# Board.net
KiCad netlist of a schematic drawn in Altium Designer
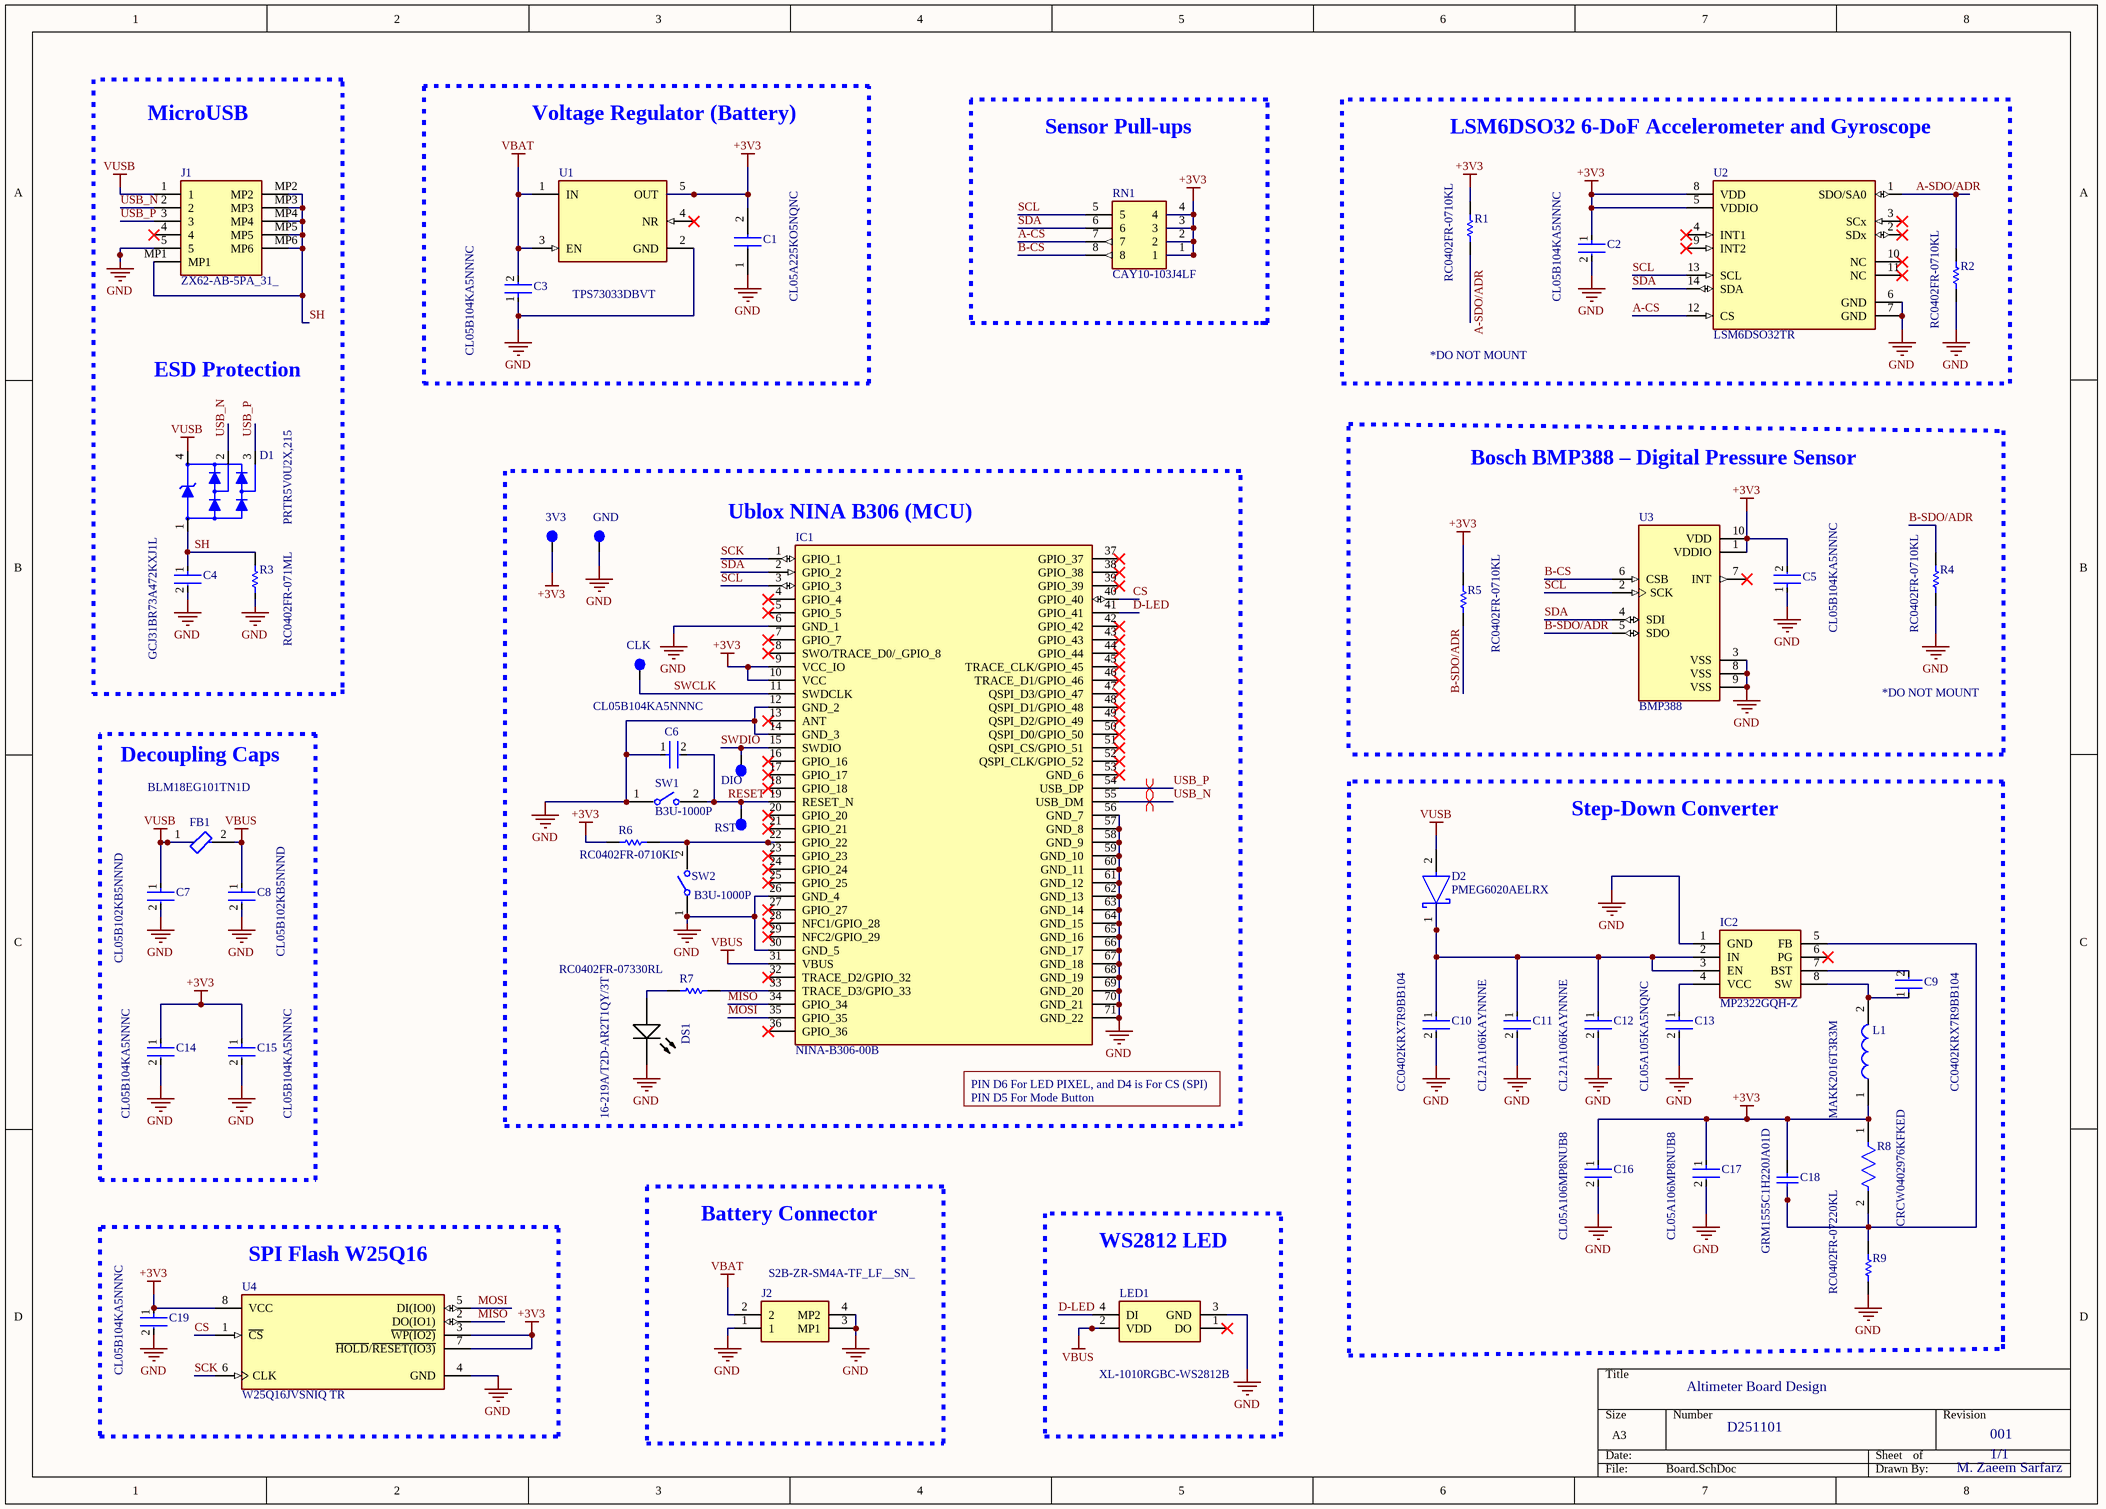
[diagram p0: Board.SchDoc]

(export (version "E")
  (design (tool "Eeschema 10.0.6"))
  (components
    (comp (ref "3V3") (value "TP_1") (footprint "TestPoint1") (libsource (lib "Schlib1") (part "TESTPOINT1")))
    (comp (ref "C1")
      (value "CL05A225KO5NQNC")
      (footprint "SamacSys:CAPC1005X60N")
      (description "Capacitor")
      (libsource (lib "*") (part "CL05A225KO5NQNC"))
    )
    (comp (ref "C2")
      (value "CL05B104KA5NNNC")
      (footprint "FP-CL830-IPC_C")
      (description "Cap Ceramic 100nF 25V X7R ±10% SMD 0402 +125°C Paper T/R")
      (fields (field (name "TOLERANCE") "10%"))
      (libsource (lib "Altium Content Vault") (part "b4654b650e69147ec39a6b967a45e02"))
    )
    (comp (ref "C3")
      (value "CL05B104KA5NNNC")
      (footprint "FP-CL830-IPC_C")
      (description "Cap Ceramic 100nF 25V X7R ±10% SMD 0402 +125°C Paper T/R")
      (fields (field (name "TOLERANCE") "10%"))
      (libsource (lib "Altium Content Vault") (part "b4654b650e69147ec39a6b967a45e02"))
    )
    (comp (ref "C4")
      (value "GCJ31BR73A472KXJ1L")
      (footprint "FP-GCJ31B-0_2-MFG")
      (description "4700pF ±10%  1kV Ceramic Capacitor X7R 1206 (3216 Metric)")
      (fields (field (name "TOLERANCE") "10%"))
      (libsource (lib "Altium Content Vault") (part "b4654b650e69147ec39a6b967a45e02"))
    )
    (comp (ref "C5")
      (value "CL05B104KA5NNNC")
      (footprint "FP-CL830-IPC_C")
      (description "Cap Ceramic 100nF 25V X7R ±10% SMD 0402 +125°C Paper T/R")
      (fields (field (name "TOLERANCE") "10%"))
      (libsource (lib "Altium Content Vault") (part "b4654b650e69147ec39a6b967a45e02"))
    )
    (comp (ref "C6")
      (value "CL05B104KA5NNNC")
      (footprint "FP-CL830-IPC_C")
      (description "Cap Ceramic 100nF 25V X7R ±10% SMD 0402 +125°C Paper T/R")
      (fields (field (name "TOLERANCE") "10%"))
      (libsource (lib "Altium Content Vault") (part "b4654b650e69147ec39a6b967a45e02"))
    )
    (comp (ref "C7")
      (value "CL05B102KB5NNND")
      (footprint "FP-CL134-IPC_C")
      (description "Cap Ceramic 1nF 50V X7R ±10% SMD 0402 +125°C Paper T/R")
      (fields (field (name "VOLTAGE") "50V") (field (name "TOLERANCE") "10%"))
      (libsource (lib "Altium Content Vault") (part "b4654b650e69147ec39a6b967a45e02"))
    )
    (comp (ref "C8")
      (value "CL05B102KB5NNND")
      (footprint "FP-CL134-IPC_C")
      (description "Cap Ceramic 1nF 50V X7R ±10% SMD 0402 +125°C Paper T/R")
      (fields (field (name "VOLTAGE") "50V") (field (name "TOLERANCE") "10%"))
      (libsource (lib "Altium Content Vault") (part "b4654b650e69147ec39a6b967a45e02"))
    )
    (comp (ref "C9")
      (value "CC0402KRX7R9BB104")
      (footprint "FP-CC0402-MFG")
      (description "CAP CER 0.1UF 50V X7R 0402")
      (fields
        (field (name "MANUFACTURER") "YAGEO")
        (field (name "OCTOPART") "https://octopart.com/cc0402krx7r9bb104-yageo-56536067")
      )
      (libsource (lib "Altium Content Vault") (part "11868f565c42a9108669ba33697ecf6"))
    )
    (comp (ref "C10")
      (value "CC0402KRX7R9BB104")
      (footprint "FP-CC0402-MFG")
      (description "CAP CER 0.1UF 50V X7R 0402")
      (fields
        (field (name "MANUFACTURER") "YAGEO")
        (field (name "OCTOPART") "https://octopart.com/cc0402krx7r9bb104-yageo-56536067")
      )
      (libsource (lib "Altium Content Vault") (part "11868f565c42a9108669ba33697ecf6"))
    )
    (comp (ref "C11")
      (value "CL21A106KAYNNNE")
      (footprint "FP-CL21-IPC_A")
      (description "CL21 Series 0805 10uF 25V ±10% Tolerance X5R Multilayer Ceramic Chip Capacitor")
      (fields (field (name "TOLERANCE") "10%"))
      (libsource (lib "Altium Content Vault") (part "b4654b650e69147ec39a6b967a45e02"))
    )
    (comp (ref "C12")
      (value "CL21A106KAYNNNE")
      (footprint "FP-CL21-IPC_A")
      (description "CL21 Series 0805 10uF 25V ±10% Tolerance X5R Multilayer Ceramic Chip Capacitor")
      (fields (field (name "TOLERANCE") "10%"))
      (libsource (lib "Altium Content Vault") (part "b4654b650e69147ec39a6b967a45e02"))
    )
    (comp (ref "C13")
      (value "CL05A105KA5NQNC")
      (footprint "FP-CL542-IPC_C")
      (description "Cap Ceramic 1uF 25V X5R ±10% SMD 0402 +85°C Paper T/R")
      (fields (field (name "TOLERANCE") "10%"))
      (libsource (lib "Altium Content Vault") (part "b4654b650e69147ec39a6b967a45e02"))
    )
    (comp (ref "C14")
      (value "CL05B104KA5NNNC")
      (footprint "FP-CL830-IPC_C")
      (description "Cap Ceramic 100nF 25V X7R ±10% SMD 0402 +125°C Paper T/R")
      (fields (field (name "TOLERANCE") "10%"))
      (libsource (lib "Altium Content Vault") (part "b4654b650e69147ec39a6b967a45e02"))
    )
    (comp (ref "C15")
      (value "CL05B104KA5NNNC")
      (footprint "FP-CL830-IPC_C")
      (description "Cap Ceramic 100nF 25V X7R ±10% SMD 0402 +125°C Paper T/R")
      (fields (field (name "TOLERANCE") "10%"))
      (libsource (lib "Altium Content Vault") (part "b4654b650e69147ec39a6b967a45e02"))
    )
    (comp (ref "C16")
      (value "CL05A106MP8NUB8")
      (footprint "FP-CL07-IPC_C")
      (description "Cap Ceramic 10uF 10V X5R ±20% SMD 0402 +85°C Paper T/R")
      (fields (field (name "TOLERANCE") "20%"))
      (libsource (lib "Altium Content Vault") (part "b4654b650e69147ec39a6b967a45e02"))
    )
    (comp (ref "C17")
      (value "CL05A106MP8NUB8")
      (footprint "FP-CL07-IPC_C")
      (description "Cap Ceramic 10uF 10V X5R ±20% SMD 0402 +85°C Paper T/R")
      (fields (field (name "TOLERANCE") "20%"))
      (libsource (lib "Altium Content Vault") (part "b4654b650e69147ec39a6b967a45e02"))
    )
    (comp (ref "C18")
      (value "GRM1555C1H220JA01D")
      (footprint "CAPC1005X55X25NL05T10")
      (fields (field (name "MANUFACTURER") "Murata"))
      (libsource (lib "Altium Content Vault") (part "CAP"))
    )
    (comp (ref "C19")
      (value "CL05B104KA5NNNC")
      (footprint "FP-CL830-IPC_C")
      (description "Cap Ceramic 100nF 25V X7R ±10% SMD 0402 +125°C Paper T/R")
      (fields (field (name "TOLERANCE") "10%"))
      (libsource (lib "Altium Content Vault") (part "b4654b650e69147ec39a6b967a45e02"))
    )
    (comp (ref "CLK") (value "TP_1") (footprint "TestPoint1") (libsource (lib "Schlib1") (part "TESTPOINT1")))
    (comp (ref "D1")
      (value "PRTR5V0U2X,215")
      (footprint "SOT143B")
      (description "Ultra low capacitance double rail-to-rail ESD protection diode")
      (libsource (lib "PRTR5V0U2X_215") (part "PRTR5V0U2X,215"))
    )
    (comp (ref "D2")
      (value "PMEG6020AELRX")
      (footprint "FP-SOD123W-MFG")
      (description "DIODE SCHOTTKY 60V 2A CFP3")
      (libsource (lib "Altium Content Vault") (part "1d6ec82d83fb6aee721767c19dac4b9"))
    )
    (comp (ref "DIO") (value "TP_1") (footprint "TestPoint1") (libsource (lib "Schlib1") (part "TESTPOINT1")))
    (comp (ref "DS1")
      (value "16-219A/T2D-AR2T1QY/3T")
      (footprint "EVRL-0402-2_V")
      (description "Chip LED, White, 5 V, 10 mA, 30 mW, -40 to 85 degC, 2-Pin SMD (0402), RoHS, Tape and Reel")
      (fields (field (name "MANUFACTURER") "Everlight Electronics"))
      (libsource (lib "Altium Content Vault") (part "LED-WHITE-AK-2"))
    )
    (comp (ref "FB1")
      (value "BLM18EG101TN1D")
      (footprint "FP-BLM18-0_15-t0_5-MFG")
      (description "Chip Ferrite Bead, 0603, 100Ω @ 100MHz, 25%, 0.045Ω, 2A")
      (fields (field (name "TOLERANCE") "25%"))
      (libsource (lib "Altium Content Vault") (part "5f30dd21d616792df468990f7003faa"))
    )
    (comp (ref "GND") (value "TP_1") (footprint "TestPoint1") (libsource (lib "Schlib1") (part "TESTPOINT1")))
    (comp (ref "IC1")
      (value "NINA-B306-00B")
      (footprint "SamacSys:NINAB30600B")
      (description "Integrated Circuit")
      (fields (field (name "MOUSER PART NUMBER") "377-NINA-B306-00B"))
      (libsource (lib "*") (part "NINA-B306-00B"))
    )
    (comp (ref "IC2")
      (value "MP2322GQH-Z")
      (footprint "SamacSys:MP2322GQHZ")
      (description "Integrated Circuit")
      (fields (field (name "MOUSER PART NUMBER") "946-MP2322GQH-Z"))
      (libsource (lib "*") (part "MP2322GQH-Z"))
    )
    (comp (ref "J1")
      (value "ZX62-AB-5PA_31_")
      (footprint "SamacSys:ZX62AB5PA31")
      (description "Connector")
      (fields
        (field (name "MANUFACTURER_PART_NUMBER") "ZX62-AB-5PA(31)")
        (field (name "MOUSER PART NUMBER") "798-ZX62-AB-5PA31")
      )
      (libsource (lib "*") (part "ZX62-AB-5PA_31_"))
    )
    (comp (ref "J2")
      (value "S2B-ZR-SM4A-TF_LF__SN_")
      (footprint "SamacSys:S2BZRSM4ATFLFSN")
      (description "Connector")
      (fields
        (field (name "MANUFACTURER_PART_NUMBER") "S2B-ZR-SM4A-TF(LF)(SN)")
        (field (name "MOUSER PART NUMBER") "306-S2BZRSM4ATFLFSN")
      )
      (libsource (lib "*") (part "S2B-ZR-SM4A-TF_LF__SN_"))
    )
    (comp (ref "L1")
      (value "MAKK2016T3R3M")
      (footprint "SamacSys:INDPM2016X100N")
      (description "Inductor")
      (fields (field (name "MOUSER PART NUMBER") "963-MAKK2016T3R3M"))
      (libsource (lib "*") (part "MAKK2016T3R3M"))
    )
    (comp (ref "LED1")
      (value "XL-1010RGBC-WS2812B")
      (footprint "SamacSys:XL1010RGBCWS2812B")
      (description "LED")
      (libsource (lib "*") (part "XL-1010RGBC-WS2812B"))
    )
    (comp (ref "R1")
      (value "RC0402FR-0710KL")
      (footprint "RESC1005X40X25LL05T10")
      (fields (field (name "MANUFACTURER") "Yageo / Phycomp") (field (name "MOUNT") "*DO NOT MOUNT"))
      (libsource (lib "Altium Content Vault") (part "RES"))
    )
    (comp (ref "R2")
      (value "RC0402FR-0710KL")
      (footprint "RESC1005X40X25LL05T10")
      (fields (field (name "MANUFACTURER") "Yageo / Phycomp"))
      (libsource (lib "Altium Content Vault") (part "RES"))
    )
    (comp (ref "R3")
      (value "RC0402FR-071ML")
      (footprint "RESC1005X40X25NL05T10")
      (fields (field (name "MANUFACTURER") "Yageo / Phycomp"))
      (libsource (lib "Altium Content Vault") (part "RES"))
    )
    (comp (ref "R4")
      (value "RC0402FR-0710KL")
      (footprint "RESC1005X40X25LL05T10")
      (fields (field (name "MANUFACTURER") "Yageo / Phycomp") (field (name "MOUNT") "*DO NOT MOUNT"))
      (libsource (lib "Altium Content Vault") (part "RES"))
    )
    (comp (ref "R5")
      (value "RC0402FR-0710KL")
      (footprint "RESC1005X40X25LL05T10")
      (fields (field (name "MANUFACTURER") "Yageo / Phycomp"))
      (libsource (lib "Altium Content Vault") (part "RES"))
    )
    (comp (ref "R6")
      (value "RC0402FR-0710KL")
      (footprint "RESC1005X40X25LL05T10")
      (fields (field (name "MANUFACTURER") "Yageo / Phycomp"))
      (libsource (lib "Altium Content Vault") (part "RES"))
    )
    (comp (ref "R7")
      (value "RC0402FR-07330RL")
      (footprint "RESC1005X40X25LL05T10")
      (fields (field (name "MANUFACTURER") "Yageo / Phycomp"))
      (libsource (lib "Altium Content Vault") (part "RES"))
    )
    (comp (ref "R8")
      (value "CRCW0402976KFKED")
      (footprint "FP-CRCW0402-e3-IPC_A")
      (description "RES Thick Film, 976kΩ, 1%, 0.063W, 100ppm/°C, 0402")
      (fields (field (name "TOLERANCE") "1%"))
      (libsource (lib "Altium Content Vault") (part "1029c3af85768c4190bb7ad29bc67b5"))
    )
    (comp (ref "R9")
      (value "RC0402FR-07220KL")
      (footprint "RESC1005X40X25LL05T10")
      (fields (field (name "MANUFACTURER") "Yageo / Phycomp"))
      (libsource (lib "Altium Content Vault") (part "RES"))
    )
    (comp (ref "RN1")
      (value "CAY10-103J4LF")
      (footprint "SamacSys:CAY10103J4LF")
      (description "Resistor Network")
      (fields (field (name "MOUSER PART NUMBER") "652-CAY10-103J4LF"))
      (libsource (lib "*") (part "CAY10-103J4LF"))
    )
    (comp (ref "RST") (value "TP_1") (footprint "TestPoint1") (libsource (lib "Schlib1") (part "TESTPOINT1")))
    (comp (ref "SW1")
      (value "B3U-1000P")
      (footprint "FP-B3U-1000P-MFG")
      (description "SWITCH TACTILE SPST-NO 0.05A 12V")
      (libsource (lib "Altium Content Vault") (part "ae622034201233ca1abcedc05908f33"))
    )
    (comp (ref "SW2")
      (value "B3U-1000P")
      (footprint "FP-B3U-1000P-MFG")
      (description "SWITCH TACTILE SPST-NO 0.05A 12V")
      (libsource (lib "Altium Content Vault") (part "ae622034201233ca1abcedc05908f33"))
    )
    (comp (ref "U1")
      (value "TPS73033DBVT")
      (footprint "FP-DBV0005A-IPC_A")
      (description "IC REG LINEAR 3.3V 200MA SOT23-5")
      (libsource (lib "Altium Content Vault") (part "172bf3999cc64eb5861273c6a7c7026"))
    )
    (comp (ref "U2")
      (value "LSM6DSO32TR")
      (footprint "FP-LGA-14L-DM00249496-MFG")
      (description "INEMO INERTIAL MODULE: 3D ACCELE")
      (libsource (lib "Altium Content Vault") (part "593856c316c551aebc7657d93cdb4f0"))
    )
    (comp (ref "U3")
      (value "BMP388")
      (footprint "PQFN50P200X200X80-10N")
      (description "P-Sensor SPI I2C 1, 25 Bar SMD")
      (libsource (lib "BMP388") (part "BMP388"))
    )
    (comp (ref "U4")
      (value "W25Q16JVSNIQ TR")
      (footprint "FP-W25Q16JVSNIQ_TR-IPC_A")
      (description "IC FLASH 16MBIT SPI/QUAD 8SOIC")
      (libsource (lib "Altium Content Vault") (part "bca9062cdd4fd3591131373229c4e34"))
    )
  )
  (nets
    (net (code "1") (name "+3V3") (class "Default")
      (node (ref "3V3") (pin "TP1") (pinfunction "1_TP1") (pintype "passive"))
      (node (ref "C1") (pin "2") (pinfunction "2_2") (pintype "passive"))
      (node (ref "C14") (pin "1") (pinfunction "1_1") (pintype "passive"))
      (node (ref "C15") (pin "1") (pinfunction "1_1") (pintype "passive"))
      (node (ref "C16") (pin "1") (pinfunction "1_1") (pintype "passive"))
      (node (ref "C17") (pin "1") (pinfunction "1_1") (pintype "passive"))
      (node (ref "C18") (pin "2") (pinfunction "2_2") (pintype "passive"))
      (node (ref "C19") (pin "1") (pinfunction "1_1") (pintype "passive"))
      (node (ref "C2") (pin "1") (pinfunction "1_1") (pintype "passive"))
      (node (ref "C5") (pin "2") (pinfunction "2_2") (pintype "passive"))
      (node (ref "IC1") (pin "10") (pinfunction "VCC_10") (pintype "passive"))
      (node (ref "IC1") (pin "9") (pinfunction "VCC_IO_9") (pintype "passive"))
      (node (ref "L1") (pin "1") (pinfunction "1_1") (pintype "passive"))
      (node (ref "R1") (pin "2") (pinfunction "2_2") (pintype "passive"))
      (node (ref "R5") (pin "2") (pinfunction "2_2") (pintype "passive"))
      (node (ref "R6") (pin "2") (pinfunction "2_2") (pintype "passive"))
      (node (ref "R8") (pin "1") (pinfunction "1_1") (pintype "passive"))
      (node (ref "RN1") (pin "1") (pinfunction "1_1") (pintype "passive"))
      (node (ref "RN1") (pin "2") (pinfunction "2_2") (pintype "passive"))
      (node (ref "RN1") (pin "3") (pinfunction "3_3") (pintype "passive"))
      (node (ref "RN1") (pin "4") (pinfunction "4_4") (pintype "passive"))
      (node (ref "U1") (pin "5") (pinfunction "OUT_5") (pintype "power_in"))
      (node (ref "U2") (pin "5") (pinfunction "VDDIO_5") (pintype "power_in"))
      (node (ref "U2") (pin "8") (pinfunction "VDD_8") (pintype "power_in"))
      (node (ref "U3") (pin "1") (pinfunction "VDDIO_1") (pintype "power_in"))
      (node (ref "U3") (pin "10") (pinfunction "VDD_10") (pintype "power_in"))
      (node (ref "U4") (pin "3") (pinfunction "~{WP(IO2)}_3") (pintype "power_in"))
      (node (ref "U4") (pin "7") (pinfunction "~{HOLD}/~{RESET(IO3)}_7") (pintype "power_in"))
      (node (ref "U4") (pin "8") (pinfunction "VCC_8") (pintype "power_in"))
    )
    (net (code "2") (name "/A-CS") (class "Default")
      (node (ref "RN1") (pin "7") (pinfunction "7_7") (pintype "output"))
      (node (ref "U2") (pin "12") (pinfunction "CS_12") (pintype "input"))
    )
    (net (code "3") (name "/A-SDO{slash}ADR") (class "Default")
      (node (ref "R1") (pin "1") (pinfunction "1_1") (pintype "passive"))
      (node (ref "R2") (pin "2") (pinfunction "2_2") (pintype "passive"))
      (node (ref "U2") (pin "1") (pinfunction "SDO/SA0_1") (pintype "bidirectional"))
    )
    (net (code "4") (name "/B-CS") (class "Default")
      (node (ref "RN1") (pin "8") (pinfunction "8_8") (pintype "output"))
      (node (ref "U3") (pin "6") (pinfunction "CSB_6") (pintype "input"))
    )
    (net (code "5") (name "/B-SDO{slash}ADR") (class "Default")
      (node (ref "R4") (pin "2") (pinfunction "2_2") (pintype "passive"))
      (node (ref "R5") (pin "1") (pinfunction "1_1") (pintype "passive"))
      (node (ref "U3") (pin "5") (pinfunction "SDO_5") (pintype "bidirectional"))
    )
    (net (code "6") (name "/CS") (class "Default")
      (node (ref "IC1") (pin "40") (pinfunction "GPIO_40_40") (pintype "bidirectional"))
      (node (ref "U4") (pin "1") (pinfunction "~{CS}_1") (pintype "input"))
    )
    (net (code "7") (name "/D-LED") (class "Default")
      (node (ref "IC1") (pin "41") (pinfunction "GPIO_41_41") (pintype "passive"))
      (node (ref "LED1") (pin "4") (pinfunction "DI_4") (pintype "passive"))
    )
    (net (code "8") (name "/MISO") (class "Default")
      (node (ref "IC1") (pin "34") (pinfunction "GPIO_34_34") (pintype "passive"))
      (node (ref "U4") (pin "2") (pinfunction "DO(IO1)_2") (pintype "bidirectional"))
    )
    (net (code "9") (name "/MOSI") (class "Default")
      (node (ref "IC1") (pin "35") (pinfunction "GPIO_35_35") (pintype "passive"))
      (node (ref "U4") (pin "5") (pinfunction "DI(IO0)_5") (pintype "bidirectional"))
    )
    (net (code "10") (name "/RESET") (class "Default")
      (node (ref "C6") (pin "2") (pinfunction "2_2") (pintype "passive"))
      (node (ref "IC1") (pin "19") (pinfunction "RESET_N_19") (pintype "passive"))
      (node (ref "RST") (pin "TP1") (pinfunction "1_TP1") (pintype "passive"))
      (node (ref "SW1") (pin "2") (pinfunction "2_2") (pintype "passive"))
    )
    (net (code "11") (name "/SCK") (class "Default")
      (node (ref "IC1") (pin "1") (pinfunction "GPIO_1_1") (pintype "bidirectional"))
      (node (ref "U4") (pin "6") (pinfunction "CLK_6") (pintype "input"))
    )
    (net (code "12") (name "/SCL") (class "Default")
      (node (ref "IC1") (pin "3") (pinfunction "GPIO_3_3") (pintype "bidirectional"))
      (node (ref "RN1") (pin "5") (pinfunction "5_5") (pintype "passive"))
      (node (ref "U2") (pin "13") (pinfunction "SCL_13") (pintype "input"))
      (node (ref "U3") (pin "2") (pinfunction "SCK_2") (pintype "input"))
    )
    (net (code "13") (name "/SDA") (class "Default")
      (node (ref "IC1") (pin "2") (pinfunction "GPIO_2_2") (pintype "input"))
      (node (ref "RN1") (pin "6") (pinfunction "6_6") (pintype "passive"))
      (node (ref "U2") (pin "14") (pinfunction "SDA_14") (pintype "bidirectional"))
      (node (ref "U3") (pin "4") (pinfunction "SDI_4") (pintype "bidirectional"))
    )
    (net (code "14") (name "/SH") (class "Default")
      (node (ref "C4") (pin "1") (pinfunction "1_1") (pintype "passive"))
      (node (ref "D1") (pin "1") (pinfunction "P$1_1") (pintype "passive"))
      (node (ref "J1") (pin "MP1") (pinfunction "MP1_MP1") (pintype "passive"))
      (node (ref "J1") (pin "MP2") (pinfunction "MP2_MP2") (pintype "passive"))
      (node (ref "J1") (pin "MP3") (pinfunction "MP3_MP3") (pintype "passive"))
      (node (ref "J1") (pin "MP4") (pinfunction "MP4_MP4") (pintype "passive"))
      (node (ref "J1") (pin "MP5") (pinfunction "MP5_MP5") (pintype "passive"))
      (node (ref "J1") (pin "MP6") (pinfunction "MP6_MP6") (pintype "passive"))
      (node (ref "R3") (pin "2") (pinfunction "2_2") (pintype "passive"))
    )
    (net (code "15") (name "/SWCLK") (class "Default")
      (node (ref "CLK") (pin "TP1") (pinfunction "1_TP1") (pintype "passive"))
      (node (ref "IC1") (pin "11") (pinfunction "SWDCLK_11") (pintype "passive"))
    )
    (net (code "16") (name "/SWDIO") (class "Default")
      (node (ref "DIO") (pin "TP1") (pinfunction "1_TP1") (pintype "passive"))
      (node (ref "IC1") (pin "15") (pinfunction "SWDIO_15") (pintype "passive"))
    )
    (net (code "17") (name "/USB_N") (class "Default")
      (node (ref "D1") (pin "2") (pinfunction "P$2_2") (pintype "passive"))
      (node (ref "IC1") (pin "55") (pinfunction "USB_DM_55") (pintype "passive"))
      (node (ref "J1") (pin "2") (pinfunction "2_2") (pintype "passive"))
    )
    (net (code "18") (name "/USB_P") (class "Default")
      (node (ref "D1") (pin "3") (pinfunction "P$3_3") (pintype "passive"))
      (node (ref "IC1") (pin "54") (pinfunction "USB_DP_54") (pintype "passive"))
      (node (ref "J1") (pin "3") (pinfunction "3_3") (pintype "passive"))
    )
    (net (code "19") (name "GND") (class "Default")
      (node (ref "C1") (pin "1") (pinfunction "1_1") (pintype "passive"))
      (node (ref "C10") (pin "2") (pinfunction "2_2") (pintype "passive"))
      (node (ref "C11") (pin "2") (pinfunction "2_2") (pintype "passive"))
      (node (ref "C12") (pin "2") (pinfunction "2_2") (pintype "passive"))
      (node (ref "C13") (pin "2") (pinfunction "2_2") (pintype "passive"))
      (node (ref "C14") (pin "2") (pinfunction "2_2") (pintype "passive"))
      (node (ref "C15") (pin "2") (pinfunction "2_2") (pintype "passive"))
      (node (ref "C16") (pin "2") (pinfunction "2_2") (pintype "passive"))
      (node (ref "C17") (pin "2") (pinfunction "2_2") (pintype "passive"))
      (node (ref "C19") (pin "2") (pinfunction "2_2") (pintype "passive"))
      (node (ref "C2") (pin "2") (pinfunction "2_2") (pintype "passive"))
      (node (ref "C3") (pin "1") (pinfunction "1_1") (pintype "passive"))
      (node (ref "C4") (pin "2") (pinfunction "2_2") (pintype "passive"))
      (node (ref "C5") (pin "1") (pinfunction "1_1") (pintype "passive"))
      (node (ref "C6") (pin "1") (pinfunction "1_1") (pintype "passive"))
      (node (ref "C7") (pin "2") (pinfunction "2_2") (pintype "passive"))
      (node (ref "C8") (pin "2") (pinfunction "2_2") (pintype "passive"))
      (node (ref "DS1") (pin "2") (pinfunction "K_2") (pintype "passive"))
      (node (ref "GND") (pin "TP1") (pinfunction "1_TP1") (pintype "passive"))
      (node (ref "IC1") (pin "12") (pinfunction "GND_2_12") (pintype "passive"))
      (node (ref "IC1") (pin "14") (pinfunction "GND_3_14") (pintype "passive"))
      (node (ref "IC1") (pin "26") (pinfunction "GND_4_26") (pintype "passive"))
      (node (ref "IC1") (pin "30") (pinfunction "GND_5_30") (pintype "passive"))
      (node (ref "IC1") (pin "56") (pinfunction "GND_7_56") (pintype "passive"))
      (node (ref "IC1") (pin "57") (pinfunction "GND_8_57") (pintype "passive"))
      (node (ref "IC1") (pin "58") (pinfunction "GND_9_58") (pintype "passive"))
      (node (ref "IC1") (pin "59") (pinfunction "GND_10_59") (pintype "passive"))
      (node (ref "IC1") (pin "6") (pinfunction "GND_1_6") (pintype "passive"))
      (node (ref "IC1") (pin "60") (pinfunction "GND_11_60") (pintype "passive"))
      (node (ref "IC1") (pin "61") (pinfunction "GND_12_61") (pintype "passive"))
      (node (ref "IC1") (pin "62") (pinfunction "GND_13_62") (pintype "passive"))
      (node (ref "IC1") (pin "63") (pinfunction "GND_14_63") (pintype "passive"))
      (node (ref "IC1") (pin "64") (pinfunction "GND_15_64") (pintype "passive"))
      (node (ref "IC1") (pin "65") (pinfunction "GND_16_65") (pintype "passive"))
      (node (ref "IC1") (pin "66") (pinfunction "GND_17_66") (pintype "passive"))
      (node (ref "IC1") (pin "67") (pinfunction "GND_18_67") (pintype "passive"))
      (node (ref "IC1") (pin "68") (pinfunction "GND_19_68") (pintype "passive"))
      (node (ref "IC1") (pin "69") (pinfunction "GND_20_69") (pintype "passive"))
      (node (ref "IC1") (pin "70") (pinfunction "GND_21_70") (pintype "passive"))
      (node (ref "IC1") (pin "71") (pinfunction "GND_22_71") (pintype "passive"))
      (node (ref "IC2") (pin "1") (pinfunction "GND_1") (pintype "passive"))
      (node (ref "J1") (pin "5") (pinfunction "5_5") (pintype "passive"))
      (node (ref "J2") (pin "1") (pinfunction "1_1") (pintype "passive"))
      (node (ref "J2") (pin "3") (pinfunction "MP1_3") (pintype "passive"))
      (node (ref "J2") (pin "4") (pinfunction "MP2_4") (pintype "passive"))
      (node (ref "LED1") (pin "3") (pinfunction "GND_3") (pintype "passive"))
      (node (ref "R2") (pin "1") (pinfunction "1_1") (pintype "passive"))
      (node (ref "R3") (pin "1") (pinfunction "1_1") (pintype "passive"))
      (node (ref "R4") (pin "1") (pinfunction "1_1") (pintype "passive"))
      (node (ref "R9") (pin "2") (pinfunction "2_2") (pintype "passive"))
      (node (ref "SW1") (pin "1") (pinfunction "1_1") (pintype "passive"))
      (node (ref "SW2") (pin "1") (pinfunction "1_1") (pintype "passive"))
      (node (ref "U1") (pin "2") (pinfunction "GND_2") (pintype "power_in"))
      (node (ref "U2") (pin "6") (pinfunction "GND_6") (pintype "power_in"))
      (node (ref "U2") (pin "7") (pinfunction "GND_7") (pintype "power_in"))
      (node (ref "U3") (pin "3") (pinfunction "VSS_3") (pintype "power_in"))
      (node (ref "U3") (pin "8") (pinfunction "VSS_8") (pintype "power_in"))
      (node (ref "U3") (pin "9") (pinfunction "VSS_9") (pintype "power_in"))
      (node (ref "U4") (pin "4") (pinfunction "GND_4") (pintype "power_in"))
    )
    (net (code "20") (name "Net-(D2-C)") (class "Default")
      (node (ref "C10") (pin "1") (pinfunction "1_1") (pintype "passive"))
      (node (ref "C11") (pin "1") (pinfunction "1_1") (pintype "passive"))
      (node (ref "C12") (pin "1") (pinfunction "1_1") (pintype "passive"))
      (node (ref "D2") (pin "1") (pinfunction "C_1") (pintype "passive"))
      (node (ref "IC2") (pin "2") (pinfunction "IN_2") (pintype "passive"))
      (node (ref "IC2") (pin "3") (pinfunction "EN_3") (pintype "passive"))
    )
    (net (code "21") (name "Net-(DS1-A)") (class "Default")
      (node (ref "DS1") (pin "1") (pinfunction "A_1") (pintype "passive"))
      (node (ref "R7") (pin "1") (pinfunction "1_1") (pintype "passive"))
    )
    (net (code "22") (name "Net-(IC1-GPIO_22)") (class "Default")
      (node (ref "IC1") (pin "22") (pinfunction "GPIO_22_22") (pintype "passive"))
      (node (ref "R6") (pin "1") (pinfunction "1_1") (pintype "passive"))
      (node (ref "SW2") (pin "2") (pinfunction "2_2") (pintype "passive"))
    )
    (net (code "23") (name "Net-(IC1-TRACE_D3{slash}GPIO_33)") (class "Default")
      (node (ref "IC1") (pin "33") (pinfunction "TRACE_D3/GPIO_33_33") (pintype "passive"))
      (node (ref "R7") (pin "2") (pinfunction "2_2") (pintype "passive"))
    )
    (net (code "24") (name "Net-(IC2-BST)") (class "Default")
      (node (ref "C9") (pin "2") (pinfunction "2_2") (pintype "passive"))
      (node (ref "IC2") (pin "7") (pinfunction "BST_7") (pintype "passive"))
    )
    (net (code "25") (name "Net-(IC2-FB)") (class "Default")
      (node (ref "C18") (pin "1") (pinfunction "1_1") (pintype "passive"))
      (node (ref "IC2") (pin "5") (pinfunction "FB_5") (pintype "passive"))
      (node (ref "R8") (pin "2") (pinfunction "2_2") (pintype "passive"))
      (node (ref "R9") (pin "1") (pinfunction "1_1") (pintype "passive"))
    )
    (net (code "26") (name "Net-(IC2-SW)") (class "Default")
      (node (ref "C9") (pin "1") (pinfunction "1_1") (pintype "passive"))
      (node (ref "IC2") (pin "8") (pinfunction "SW_8") (pintype "passive"))
      (node (ref "L1") (pin "2") (pinfunction "2_2") (pintype "passive"))
    )
    (net (code "27") (name "Net-(IC2-VCC)") (class "Default")
      (node (ref "C13") (pin "1") (pinfunction "1_1") (pintype "passive"))
      (node (ref "IC2") (pin "4") (pinfunction "VCC_4") (pintype "passive"))
    )
    (net (code "28") (name "VBAT") (class "Default")
      (node (ref "C3") (pin "2") (pinfunction "2_2") (pintype "passive"))
      (node (ref "J2") (pin "2") (pinfunction "2_2") (pintype "passive"))
      (node (ref "U1") (pin "1") (pinfunction "IN_1") (pintype "power_in"))
      (node (ref "U1") (pin "3") (pinfunction "EN_3") (pintype "input"))
    )
    (net (code "29") (name "VBUS") (class "Default")
      (node (ref "C8") (pin "1") (pinfunction "1_1") (pintype "passive"))
      (node (ref "FB1") (pin "2") (pinfunction "2_2") (pintype "passive"))
      (node (ref "IC1") (pin "31") (pinfunction "VBUS_31") (pintype "passive"))
      (node (ref "LED1") (pin "2") (pinfunction "VDD_2") (pintype "passive"))
    )
    (net (code "30") (name "VUSB") (class "Default")
      (node (ref "C7") (pin "1") (pinfunction "1_1") (pintype "passive"))
      (node (ref "D1") (pin "4") (pinfunction "P$4_4") (pintype "passive"))
      (node (ref "D2") (pin "2") (pinfunction "A_2") (pintype "passive"))
      (node (ref "FB1") (pin "1") (pinfunction "1_1") (pintype "passive"))
      (node (ref "J1") (pin "1") (pinfunction "1_1") (pintype "passive"))
    )
    (net (code "31") (name "unconnected-(IC1-ANT-Pad13)") (class "Default")
      (node (ref "IC1") (pin "13") (pinfunction "ANT_13") (pintype "passive+no_connect"))
    )
    (net (code "32") (name "unconnected-(IC1-GND_6-Pad53)") (class "Default")
      (node (ref "IC1") (pin "53") (pinfunction "GND_6_53") (pintype "passive+no_connect"))
    )
    (net (code "33") (name "unconnected-(IC1-GPIO_4-Pad4)") (class "Default")
      (node (ref "IC1") (pin "4") (pinfunction "GPIO_4_4") (pintype "passive+no_connect"))
    )
    (net (code "34") (name "unconnected-(IC1-GPIO_5-Pad5)") (class "Default")
      (node (ref "IC1") (pin "5") (pinfunction "GPIO_5_5") (pintype "passive+no_connect"))
    )
    (net (code "35") (name "unconnected-(IC1-GPIO_7-Pad7)") (class "Default")
      (node (ref "IC1") (pin "7") (pinfunction "GPIO_7_7") (pintype "passive+no_connect"))
    )
    (net (code "36") (name "unconnected-(IC1-GPIO_16-Pad16)") (class "Default")
      (node (ref "IC1") (pin "16") (pinfunction "GPIO_16_16") (pintype "passive+no_connect"))
    )
    (net (code "37") (name "unconnected-(IC1-GPIO_17-Pad17)") (class "Default")
      (node (ref "IC1") (pin "17") (pinfunction "GPIO_17_17") (pintype "passive+no_connect"))
    )
    (net (code "38") (name "unconnected-(IC1-GPIO_18-Pad18)") (class "Default")
      (node (ref "IC1") (pin "18") (pinfunction "GPIO_18_18") (pintype "passive+no_connect"))
    )
    (net (code "39") (name "unconnected-(IC1-GPIO_20-Pad20)") (class "Default")
      (node (ref "IC1") (pin "20") (pinfunction "GPIO_20_20") (pintype "passive+no_connect"))
    )
    (net (code "40") (name "unconnected-(IC1-GPIO_21-Pad21)") (class "Default")
      (node (ref "IC1") (pin "21") (pinfunction "GPIO_21_21") (pintype "passive+no_connect"))
    )
    (net (code "41") (name "unconnected-(IC1-GPIO_23-Pad23)") (class "Default")
      (node (ref "IC1") (pin "23") (pinfunction "GPIO_23_23") (pintype "passive+no_connect"))
    )
    (net (code "42") (name "unconnected-(IC1-GPIO_24-Pad24)") (class "Default")
      (node (ref "IC1") (pin "24") (pinfunction "GPIO_24_24") (pintype "passive+no_connect"))
    )
    (net (code "43") (name "unconnected-(IC1-GPIO_25-Pad25)") (class "Default")
      (node (ref "IC1") (pin "25") (pinfunction "GPIO_25_25") (pintype "passive+no_connect"))
    )
    (net (code "44") (name "unconnected-(IC1-GPIO_27-Pad27)") (class "Default")
      (node (ref "IC1") (pin "27") (pinfunction "GPIO_27_27") (pintype "passive+no_connect"))
    )
    (net (code "45") (name "unconnected-(IC1-GPIO_36-Pad36)") (class "Default")
      (node (ref "IC1") (pin "36") (pinfunction "GPIO_36_36") (pintype "passive+no_connect"))
    )
    (net (code "46") (name "unconnected-(IC1-GPIO_37-Pad37)") (class "Default")
      (node (ref "IC1") (pin "37") (pinfunction "GPIO_37_37") (pintype "passive+no_connect"))
    )
    (net (code "47") (name "unconnected-(IC1-GPIO_38-Pad38)") (class "Default")
      (node (ref "IC1") (pin "38") (pinfunction "GPIO_38_38") (pintype "passive+no_connect"))
    )
    (net (code "48") (name "unconnected-(IC1-GPIO_39-Pad39)") (class "Default")
      (node (ref "IC1") (pin "39") (pinfunction "GPIO_39_39") (pintype "passive+no_connect"))
    )
    (net (code "49") (name "unconnected-(IC1-GPIO_42-Pad42)") (class "Default")
      (node (ref "IC1") (pin "42") (pinfunction "GPIO_42_42") (pintype "passive+no_connect"))
    )
    (net (code "50") (name "unconnected-(IC1-GPIO_43-Pad43)") (class "Default")
      (node (ref "IC1") (pin "43") (pinfunction "GPIO_43_43") (pintype "passive+no_connect"))
    )
    (net (code "51") (name "unconnected-(IC1-GPIO_44-Pad44)") (class "Default")
      (node (ref "IC1") (pin "44") (pinfunction "GPIO_44_44") (pintype "passive+no_connect"))
    )
    (net (code "52") (name "unconnected-(IC1-NFC1{slash}GPIO_28-Pad28)") (class "Default")
      (node (ref "IC1") (pin "28") (pinfunction "NFC1/GPIO_28_28") (pintype "passive+no_connect"))
    )
    (net (code "53") (name "unconnected-(IC1-NFC2{slash}GPIO_29-Pad29)") (class "Default")
      (node (ref "IC1") (pin "29") (pinfunction "NFC2/GPIO_29_29") (pintype "passive+no_connect"))
    )
    (net (code "54") (name "unconnected-(IC1-QSPI_CLK{slash}GPIO_52-Pad52)") (class "Default")
      (node (ref "IC1") (pin "52") (pinfunction "QSPI_CLK/GPIO_52_52") (pintype "passive+no_connect"))
    )
    (net (code "55") (name "unconnected-(IC1-QSPI_CS{slash}GPIO_51-Pad51)") (class "Default")
      (node (ref "IC1") (pin "51") (pinfunction "QSPI_CS/GPIO_51_51") (pintype "passive+no_connect"))
    )
    (net (code "56") (name "unconnected-(IC1-QSPI_D0{slash}GPIO_50-Pad50)") (class "Default")
      (node (ref "IC1") (pin "50") (pinfunction "QSPI_D0/GPIO_50_50") (pintype "passive+no_connect"))
    )
    (net (code "57") (name "unconnected-(IC1-QSPI_D1{slash}GPIO_48-Pad48)") (class "Default")
      (node (ref "IC1") (pin "48") (pinfunction "QSPI_D1/GPIO_48_48") (pintype "passive+no_connect"))
    )
    (net (code "58") (name "unconnected-(IC1-QSPI_D2{slash}GPIO_49-Pad49)") (class "Default")
      (node (ref "IC1") (pin "49") (pinfunction "QSPI_D2/GPIO_49_49") (pintype "passive+no_connect"))
    )
    (net (code "59") (name "unconnected-(IC1-QSPI_D3{slash}GPIO_47-Pad47)") (class "Default")
      (node (ref "IC1") (pin "47") (pinfunction "QSPI_D3/GPIO_47_47") (pintype "passive+no_connect"))
    )
    (net (code "60") (name "unconnected-(IC1-SWO{slash}TRACE_D0{slash}_GPIO_8-Pad8)") (class "Default")
      (node (ref "IC1") (pin "8") (pinfunction "SWO/TRACE_D0/_GPIO_8_8") (pintype "passive+no_connect"))
    )
    (net (code "61") (name "unconnected-(IC1-TRACE_CLK{slash}GPIO_45-Pad45)") (class "Default")
      (node (ref "IC1") (pin "45") (pinfunction "TRACE_CLK/GPIO_45_45") (pintype "passive+no_connect"))
    )
    (net (code "62") (name "unconnected-(IC1-TRACE_D1{slash}GPIO_46-Pad46)") (class "Default")
      (node (ref "IC1") (pin "46") (pinfunction "TRACE_D1/GPIO_46_46") (pintype "passive+no_connect"))
    )
    (net (code "63") (name "unconnected-(IC1-TRACE_D2{slash}GPIO_32-Pad32)") (class "Default")
      (node (ref "IC1") (pin "32") (pinfunction "TRACE_D2/GPIO_32_32") (pintype "passive+no_connect"))
    )
    (net (code "64") (name "unconnected-(IC2-PG-Pad6)") (class "Default")
      (node (ref "IC2") (pin "6") (pinfunction "PG_6") (pintype "passive+no_connect"))
    )
    (net (code "65") (name "unconnected-(J1-Pad4)") (class "Default")
      (node (ref "J1") (pin "4") (pinfunction "4_4") (pintype "passive+no_connect"))
    )
    (net (code "66") (name "unconnected-(LED1-DO-Pad1)") (class "Default")
      (node (ref "LED1") (pin "1") (pinfunction "DO_1") (pintype "passive+no_connect"))
    )
    (net (code "67") (name "unconnected-(U1-NR-Pad4)") (class "Default")
      (node (ref "U1") (pin "4") (pinfunction "NR_4") (pintype "input+no_connect"))
    )
    (net (code "68") (name "unconnected-(U2-INT1-Pad4)") (class "Default")
      (node (ref "U2") (pin "4") (pinfunction "INT1_4") (pintype "input+no_connect"))
    )
    (net (code "69") (name "unconnected-(U2-INT2-Pad9)") (class "Default")
      (node (ref "U2") (pin "9") (pinfunction "INT2_9") (pintype "input+no_connect"))
    )
    (net (code "70") (name "unconnected-(U2-NC-Pad10)") (class "Default")
      (node (ref "U2") (pin "10") (pinfunction "NC_10") (pintype "passive+no_connect"))
    )
    (net (code "71") (name "unconnected-(U2-NC-Pad11)") (class "Default")
      (node (ref "U2") (pin "11") (pinfunction "NC_11") (pintype "passive+no_connect"))
    )
    (net (code "72") (name "unconnected-(U2-SCx-Pad3)") (class "Default")
      (node (ref "U2") (pin "3") (pinfunction "SCx_3") (pintype "input+no_connect"))
    )
    (net (code "73") (name "unconnected-(U2-SDx-Pad2)") (class "Default")
      (node (ref "U2") (pin "2") (pinfunction "SDx_2") (pintype "bidirectional+no_connect"))
    )
    (net (code "74") (name "unconnected-(U3-INT-Pad7)") (class "Default")
      (node (ref "U3") (pin "7") (pinfunction "INT_7") (pintype "output+no_connect"))
    )
  )
)
